# avga_TTH.net
KiCad netlist of a schematic drawn in EAGLE
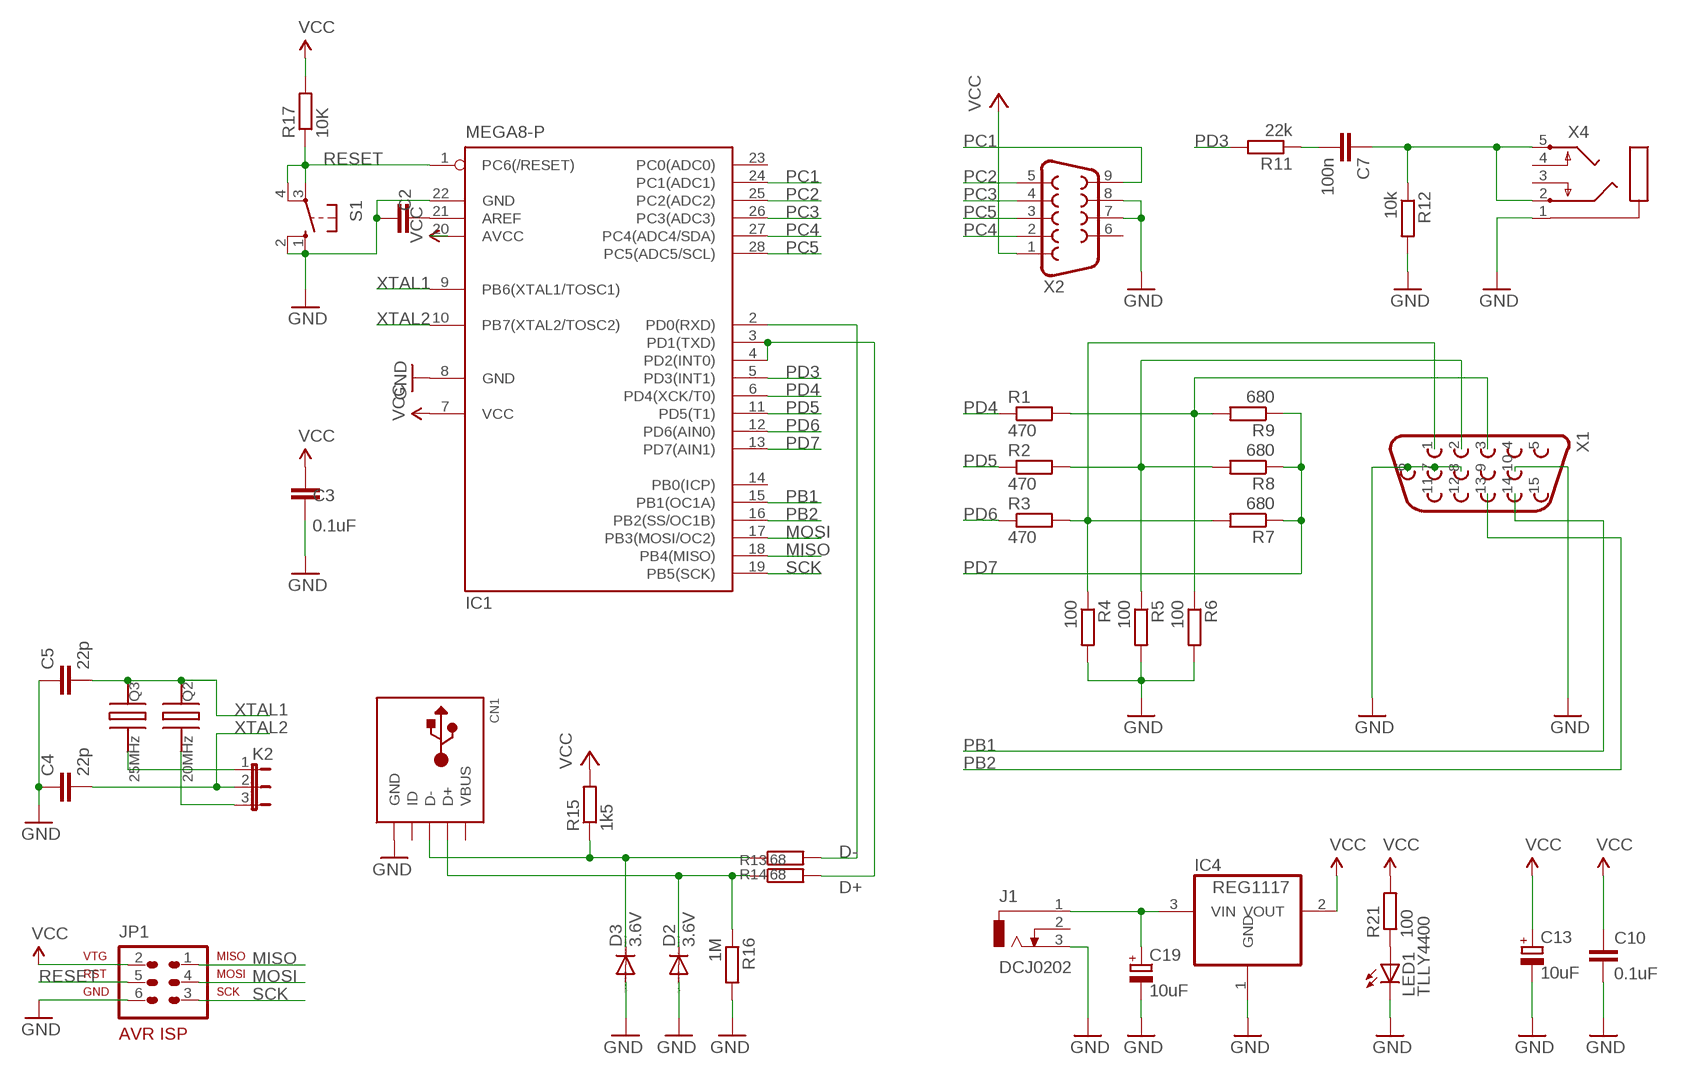
[diagram p0: schematic, sheet 1]

(export (version "E")
  (design (tool "Eeschema 10.0.6"))
  (components
    (comp (ref "C2")
      (value "0.1uF")
      (footprint "eagle-import:C0805")
      (libsource (lib "eagle-import") (part "resistor_C-EUC0805"))
    )
    (comp (ref "C3")
      (value "0.1uF")
      (footprint "eagle-import:C0805")
      (libsource (lib "eagle-import") (part "resistor_C-EUC0805"))
    )
    (comp (ref "C4")
      (value "22p")
      (footprint "eagle-import:C0805")
      (libsource (lib "eagle-import") (part "C-EUC0805"))
    )
    (comp (ref "C5")
      (value "22p")
      (footprint "eagle-import:C0805")
      (libsource (lib "eagle-import") (part "C-EUC0805"))
    )
    (comp (ref "C7")
      (value "100n")
      (footprint "eagle-import:C0805")
      (libsource (lib "eagle-import") (part "C-EUC0805"))
    )
    (comp (ref "C10")
      (value "0.1uF")
      (footprint "eagle-import:C0805")
      (libsource (lib "eagle-import") (part "C-EUC0805"))
    )
    (comp (ref "C13")
      (value "10uF")
      (footprint "eagle-import:E2,5-5")
      (libsource (lib "eagle-import") (part "CPOL-EUE2.5-5"))
    )
    (comp (ref "C19")
      (value "10uF")
      (footprint "eagle-import:E2,5-5")
      (libsource (lib "eagle-import") (part "CPOL-EUE2.5-5"))
    )
    (comp (ref "CN1")
      (value "USBMINIB")
      (footprint "eagle-import:USB-MINIB")
      (libsource (lib "eagle-import") (part "USBMINIB"))
    )
    (comp (ref "D2")
      (value "3.6V")
      (footprint "eagle-import:MINIMELF")
      (libsource (lib "eagle-import") (part "DIODE-MINIMELF"))
    )
    (comp (ref "D3")
      (value "3.6V")
      (footprint "eagle-import:MINIMELF")
      (libsource (lib "eagle-import") (part "DIODE-MINIMELF"))
    )
    (comp (ref "IC1")
      (value "MEGA8-P")
      (footprint "eagle-import:DIL28-3")
      (libsource (lib "eagle-import") (part "MEGA8-P"))
    )
    (comp (ref "IC4")
      (value "REG1117")
      (footprint "eagle-import:SOT223")
      (libsource (lib "eagle-import") (part "REG1117"))
    )
    (comp (ref "J1")
      (value "DCJ0202")
      (footprint "eagle-import:DCJ0202")
      (libsource (lib "eagle-import") (part "DCJ0202"))
    )
    (comp (ref "JP1")
      (value "AVR-ISP-6R")
      (footprint "eagle-import:AVR-ISP-6R")
      (libsource (lib "eagle-import") (part "AVR-ISP-6R"))
    )
    (comp (ref "K2")
      (value "CON-3-POL")
      (footprint "eagle-import:MOLEX-PSK-03")
      (libsource (lib "eagle-import") (part "CON-3-POL"))
    )
    (comp (ref "LED1")
      (value "TLLY4400")
      (footprint "eagle-import:LED3MM")
      (fields (field (name "MF") "VISHAY SEMICONDUCTOR"))
      (libsource (lib "eagle-import") (part "TLLY4400"))
    )
    (comp (ref "Q2")
      (value "20MHz")
      (footprint "eagle-import:QUARZ")
      (libsource (lib "eagle-import") (part "QUARZ"))
    )
    (comp (ref "Q3")
      (value "25MHz")
      (footprint "eagle-import:QUARZ")
      (libsource (lib "eagle-import") (part "QUARZ"))
    )
    (comp (ref "R1")
      (value "470")
      (footprint "eagle-import:R0805")
      (libsource (lib "eagle-import") (part "R-EU_R0805"))
    )
    (comp (ref "R2")
      (value "470")
      (footprint "eagle-import:R0805")
      (libsource (lib "eagle-import") (part "R-EU_R0805"))
    )
    (comp (ref "R3")
      (value "470")
      (footprint "eagle-import:R0805")
      (libsource (lib "eagle-import") (part "R-EU_R0805"))
    )
    (comp (ref "R4")
      (value "100")
      (footprint "eagle-import:R0805")
      (libsource (lib "eagle-import") (part "R-EU_R0805"))
    )
    (comp (ref "R5")
      (value "100")
      (footprint "eagle-import:R0805")
      (libsource (lib "eagle-import") (part "R-EU_R0805"))
    )
    (comp (ref "R6")
      (value "100")
      (footprint "eagle-import:R0805")
      (libsource (lib "eagle-import") (part "R-EU_R0805"))
    )
    (comp (ref "R7")
      (value "680")
      (footprint "eagle-import:R0805")
      (libsource (lib "eagle-import") (part "R-EU_R0805"))
    )
    (comp (ref "R8")
      (value "680")
      (footprint "eagle-import:R0805")
      (libsource (lib "eagle-import") (part "R-EU_R0805"))
    )
    (comp (ref "R9")
      (value "680")
      (footprint "eagle-import:R0805")
      (libsource (lib "eagle-import") (part "R-EU_R0805"))
    )
    (comp (ref "R11")
      (value "22k")
      (footprint "eagle-import:R0805")
      (libsource (lib "eagle-import") (part "R-EU_R0805"))
    )
    (comp (ref "R12")
      (value "10k")
      (footprint "eagle-import:R0805")
      (libsource (lib "eagle-import") (part "R-EU_R0805"))
    )
    (comp (ref "R13")
      (value "68")
      (footprint "eagle-import:R0805")
      (libsource (lib "eagle-import") (part "R-EU_R0805"))
    )
    (comp (ref "R14")
      (value "68")
      (footprint "eagle-import:R0805")
      (libsource (lib "eagle-import") (part "R-EU_R0805"))
    )
    (comp (ref "R15")
      (value "1k5")
      (footprint "eagle-import:R0805")
      (libsource (lib "eagle-import") (part "R-EU_R0805"))
    )
    (comp (ref "R16")
      (value "1M")
      (footprint "eagle-import:R0805")
      (libsource (lib "eagle-import") (part "R-EU_R0805"))
    )
    (comp (ref "R17")
      (value "10K")
      (footprint "eagle-import:R0805")
      (libsource (lib "eagle-import") (part "resistor_R-EU_R0805"))
    )
    (comp (ref "R21")
      (value "100")
      (footprint "eagle-import:R0805")
      (libsource (lib "eagle-import") (part "resistor_R-EU_R0805"))
    )
    (comp (ref "S1")
      (value "10-XX")
      (footprint "eagle-import:B3F-10XX")
      (fields (field (name "MPN") "B3F-1000"))
      (libsource (lib "eagle-import") (part "10-XX"))
    )
    (comp (ref "X1")
      (value "VGA-BU-15POL")
      (footprint "eagle-import:VGA-BU-15POL")
      (libsource (lib "eagle-import") (part "VGA-BU-15POL"))
    )
    (comp (ref "X2")
      (value "D-SUB-ST-9POL")
      (footprint "eagle-import:M09HP")
      (libsource (lib "eagle-import") (part "D-SUB-ST-9POL"))
    )
    (comp (ref "X4")
      (value "KLINKENBUCHSE")
      (footprint "eagle-import:KLINKENBUCHSE")
      (libsource (lib "eagle-import") (part "KLINKENBUCHSE"))
    )
  )
  (nets
    (net (code "1") (name "/MISO") (class "Default")
      (node (ref "IC1") (pin "18") (pinfunction "PB4(MISO)_18") (pintype "bidirectional"))
      (node (ref "JP1") (pin "1") (pinfunction "1_1") (pintype "passive"))
    )
    (net (code "2") (name "/MOSI") (class "Default")
      (node (ref "IC1") (pin "17") (pinfunction "PB3(MOSI/OC2)_17") (pintype "bidirectional"))
      (node (ref "JP1") (pin "4") (pinfunction "4_4") (pintype "passive"))
    )
    (net (code "3") (name "/PB1") (class "Default")
      (node (ref "IC1") (pin "15") (pinfunction "PB1(OC1A)_15") (pintype "bidirectional"))
      (node (ref "X1") (pin "14") (pinfunction "14_14") (pintype "passive"))
    )
    (net (code "4") (name "/PB2") (class "Default")
      (node (ref "IC1") (pin "16") (pinfunction "PB2(SS/OC1B)_16") (pintype "bidirectional"))
      (node (ref "X1") (pin "13") (pinfunction "13_13") (pintype "passive"))
    )
    (net (code "5") (name "/PC1") (class "Default")
      (node (ref "IC1") (pin "24") (pinfunction "PC1(ADC1)_24") (pintype "bidirectional"))
      (node (ref "X2") (pin "9") (pinfunction "9_9") (pintype "passive"))
    )
    (net (code "6") (name "/PC2") (class "Default")
      (node (ref "IC1") (pin "25") (pinfunction "PC2(ADC2)_25") (pintype "bidirectional"))
      (node (ref "X2") (pin "5") (pinfunction "5_5") (pintype "passive"))
    )
    (net (code "7") (name "/PC3") (class "Default")
      (node (ref "IC1") (pin "26") (pinfunction "PC3(ADC3)_26") (pintype "bidirectional"))
      (node (ref "X2") (pin "4") (pinfunction "4_4") (pintype "passive"))
    )
    (net (code "8") (name "/PC4") (class "Default")
      (node (ref "IC1") (pin "27") (pinfunction "PC4(ADC4/SDA)_27") (pintype "bidirectional"))
      (node (ref "X2") (pin "2") (pinfunction "2_2") (pintype "passive"))
    )
    (net (code "9") (name "/PC5") (class "Default")
      (node (ref "IC1") (pin "28") (pinfunction "PC5(ADC5/SCL)_28") (pintype "bidirectional"))
      (node (ref "X2") (pin "3") (pinfunction "3_3") (pintype "passive"))
    )
    (net (code "10") (name "/PD3") (class "Default")
      (node (ref "IC1") (pin "5") (pinfunction "PD3(INT1)_5") (pintype "bidirectional"))
      (node (ref "R11") (pin "2") (pinfunction "2_2") (pintype "passive"))
    )
    (net (code "11") (name "/PD4") (class "Default")
      (node (ref "IC1") (pin "6") (pinfunction "PD4(XCK/T0)_6") (pintype "bidirectional"))
      (node (ref "R1") (pin "1") (pinfunction "1_1") (pintype "passive"))
    )
    (net (code "12") (name "/PD5") (class "Default")
      (node (ref "IC1") (pin "11") (pinfunction "PD5(T1)_11") (pintype "bidirectional"))
      (node (ref "R2") (pin "1") (pinfunction "1_1") (pintype "passive"))
    )
    (net (code "13") (name "/PD6") (class "Default")
      (node (ref "IC1") (pin "12") (pinfunction "PD6(AIN0)_12") (pintype "bidirectional"))
      (node (ref "R3") (pin "1") (pinfunction "1_1") (pintype "passive"))
    )
    (net (code "14") (name "/PD7") (class "Default")
      (node (ref "IC1") (pin "13") (pinfunction "PD7(AIN1)_13") (pintype "bidirectional"))
      (node (ref "R7") (pin "1") (pinfunction "1_1") (pintype "passive"))
      (node (ref "R8") (pin "1") (pinfunction "1_1") (pintype "passive"))
      (node (ref "R9") (pin "1") (pinfunction "1_1") (pintype "passive"))
    )
    (net (code "15") (name "/RESET") (class "Default")
      (node (ref "IC1") (pin "1") (pinfunction "PC6(/RESET)_1") (pintype "bidirectional"))
      (node (ref "JP1") (pin "5") (pinfunction "5_5") (pintype "passive"))
      (node (ref "R17") (pin "1") (pinfunction "1_1") (pintype "passive"))
      (node (ref "S1") (pin "3") (pinfunction "P_3") (pintype "passive"))
      (node (ref "S1") (pin "4") (pinfunction "P1_4") (pintype "passive"))
    )
    (net (code "16") (name "/SCK") (class "Default")
      (node (ref "IC1") (pin "19") (pinfunction "PB5(SCK)_19") (pintype "bidirectional"))
      (node (ref "JP1") (pin "3") (pinfunction "3_3") (pintype "passive"))
    )
    (net (code "17") (name "/VBUS") (class "Default")
      (node (ref "CN1") (pin "VBUS") (pinfunction "VBUS_VBUS") (pintype "power_in"))
    )
    (net (code "18") (name "/XTAL1") (class "Default")
      (node (ref "C5") (pin "2") (pinfunction "2_2") (pintype "passive"))
      (node (ref "IC1") (pin "9") (pinfunction "PB6(XTAL1/TOSC1)_9") (pintype "bidirectional"))
      (node (ref "Q2") (pin "1") (pinfunction "1_1") (pintype "passive"))
      (node (ref "Q3") (pin "1") (pinfunction "1_1") (pintype "passive"))
    )
    (net (code "19") (name "/XTAL2") (class "Default")
      (node (ref "C4") (pin "2") (pinfunction "2_2") (pintype "passive"))
      (node (ref "IC1") (pin "10") (pinfunction "PB7(XTAL2/TOSC2)_10") (pintype "bidirectional"))
      (node (ref "K2") (pin "2") (pinfunction "2_2") (pintype "passive"))
    )
    (net (code "20") (name "GND") (class "Default")
      (node (ref "C10") (pin "2") (pinfunction "2_2") (pintype "passive"))
      (node (ref "C13") (pin "-") (pinfunction "-_-") (pintype "passive"))
      (node (ref "C19") (pin "-") (pinfunction "-_-") (pintype "passive"))
      (node (ref "C2") (pin "2") (pinfunction "2_2") (pintype "passive"))
      (node (ref "C3") (pin "1") (pinfunction "1_1") (pintype "passive"))
      (node (ref "C4") (pin "1") (pinfunction "1_1") (pintype "passive"))
      (node (ref "C5") (pin "1") (pinfunction "1_1") (pintype "passive"))
      (node (ref "CN1") (pin "GND") (pinfunction "GND_GND") (pintype "power_in"))
      (node (ref "D2") (pin "A") (pinfunction "A_A") (pintype "passive"))
      (node (ref "D3") (pin "A") (pinfunction "A_A") (pintype "passive"))
      (node (ref "IC1") (pin "22") (pinfunction "GND_22") (pintype "power_in"))
      (node (ref "IC1") (pin "8") (pinfunction "GND_8") (pintype "power_in"))
      (node (ref "IC4") (pin "1") (pinfunction "GND_1") (pintype "power_in"))
      (node (ref "J1") (pin "3") (pinfunction "3_3") (pintype "passive"))
      (node (ref "JP1") (pin "6") (pinfunction "6_6") (pintype "passive"))
      (node (ref "LED1") (pin "K") (pinfunction "C_K") (pintype "passive"))
      (node (ref "R12") (pin "2") (pinfunction "2_2") (pintype "passive"))
      (node (ref "R16") (pin "2") (pinfunction "2_2") (pintype "passive"))
      (node (ref "R4") (pin "2") (pinfunction "2_2") (pintype "passive"))
      (node (ref "R5") (pin "2") (pinfunction "2_2") (pintype "passive"))
      (node (ref "R6") (pin "2") (pinfunction "2_2") (pintype "passive"))
      (node (ref "S1") (pin "1") (pinfunction "S_1") (pintype "passive"))
      (node (ref "S1") (pin "2") (pinfunction "S1_2") (pintype "passive"))
      (node (ref "X1") (pin "10") (pinfunction "10_10") (pintype "passive"))
      (node (ref "X1") (pin "6") (pinfunction "6_6") (pintype "passive"))
      (node (ref "X1") (pin "7") (pinfunction "7_7") (pintype "passive"))
      (node (ref "X1") (pin "8") (pinfunction "8_8") (pintype "passive"))
      (node (ref "X2") (pin "7") (pinfunction "7_7") (pintype "passive"))
      (node (ref "X2") (pin "8") (pinfunction "8_8") (pintype "passive"))
      (node (ref "X4") (pin "1") (pinfunction "1_1") (pintype "passive"))
    )
    (net (code "21") (name "Net-(C7-Pad1)") (class "Default")
      (node (ref "C7") (pin "1") (pinfunction "1_1") (pintype "passive"))
      (node (ref "R12") (pin "1") (pinfunction "1_1") (pintype "passive"))
      (node (ref "X4") (pin "2") (pinfunction "2_2") (pintype "passive"))
      (node (ref "X4") (pin "5") (pinfunction "5_5") (pintype "passive"))
    )
    (net (code "22") (name "Net-(C7-Pad2)") (class "Default")
      (node (ref "C7") (pin "2") (pinfunction "2_2") (pintype "passive"))
      (node (ref "R11") (pin "1") (pinfunction "1_1") (pintype "passive"))
    )
    (net (code "23") (name "Net-(CN1-PadD+)") (class "Default")
      (node (ref "CN1") (pin "D+") (pinfunction "D+_D+") (pintype "bidirectional"))
      (node (ref "D2") (pin "C") (pinfunction "C_C") (pintype "passive"))
      (node (ref "R13") (pin "1") (pinfunction "1_1") (pintype "passive"))
      (node (ref "R16") (pin "1") (pinfunction "1_1") (pintype "passive"))
    )
    (net (code "24") (name "Net-(CN1-PadD-)") (class "Default")
      (node (ref "CN1") (pin "D-") (pinfunction "D-_D-") (pintype "bidirectional"))
      (node (ref "D3") (pin "C") (pinfunction "C_C") (pintype "passive"))
      (node (ref "R14") (pin "1") (pinfunction "1_1") (pintype "passive"))
      (node (ref "R15") (pin "1") (pinfunction "1_1") (pintype "passive"))
    )
    (net (code "25") (name "Net-(IC1-AREF)") (class "Default")
      (node (ref "C2") (pin "1") (pinfunction "1_1") (pintype "passive"))
      (node (ref "IC1") (pin "21") (pinfunction "AREF_21") (pintype "passive"))
    )
    (net (code "26") (name "Net-(IC1-PD0(RXD))") (class "Default")
      (node (ref "IC1") (pin "2") (pinfunction "PD0(RXD)_2") (pintype "bidirectional"))
      (node (ref "R14") (pin "2") (pinfunction "2_2") (pintype "passive"))
    )
    (net (code "27") (name "Net-(IC1-PD1(TXD))") (class "Default")
      (node (ref "IC1") (pin "3") (pinfunction "PD1(TXD)_3") (pintype "bidirectional"))
      (node (ref "IC1") (pin "4") (pinfunction "PD2(INT0)_4") (pintype "bidirectional"))
      (node (ref "R13") (pin "2") (pinfunction "2_2") (pintype "passive"))
    )
    (net (code "28") (name "Net-(IC4-VIN)") (class "Default")
      (node (ref "C19") (pin "+") (pinfunction "+_+") (pintype "passive"))
      (node (ref "IC4") (pin "3") (pinfunction "VIN_3") (pintype "input"))
      (node (ref "J1") (pin "1") (pinfunction "1_1") (pintype "passive"))
    )
    (net (code "29") (name "Net-(K2-Pad1)") (class "Default")
      (node (ref "K2") (pin "1") (pinfunction "1_1") (pintype "passive"))
      (node (ref "Q3") (pin "2") (pinfunction "2_2") (pintype "passive"))
    )
    (net (code "30") (name "Net-(K2-Pad3)") (class "Default")
      (node (ref "K2") (pin "3") (pinfunction "3_3") (pintype "passive"))
      (node (ref "Q2") (pin "2") (pinfunction "2_2") (pintype "passive"))
    )
    (net (code "31") (name "Net-(LED1-PadA)") (class "Default")
      (node (ref "LED1") (pin "A") (pinfunction "A_A") (pintype "passive"))
      (node (ref "R21") (pin "1") (pinfunction "1_1") (pintype "passive"))
    )
    (net (code "32") (name "Net-(R1-Pad2)") (class "Default")
      (node (ref "R1") (pin "2") (pinfunction "2_2") (pintype "passive"))
      (node (ref "R6") (pin "1") (pinfunction "1_1") (pintype "passive"))
      (node (ref "R9") (pin "2") (pinfunction "2_2") (pintype "passive"))
      (node (ref "X1") (pin "3") (pinfunction "3_3") (pintype "passive"))
    )
    (net (code "33") (name "Net-(R2-Pad2)") (class "Default")
      (node (ref "R2") (pin "2") (pinfunction "2_2") (pintype "passive"))
      (node (ref "R5") (pin "1") (pinfunction "1_1") (pintype "passive"))
      (node (ref "R8") (pin "2") (pinfunction "2_2") (pintype "passive"))
      (node (ref "X1") (pin "2") (pinfunction "2_2") (pintype "passive"))
    )
    (net (code "34") (name "Net-(R3-Pad2)") (class "Default")
      (node (ref "R3") (pin "2") (pinfunction "2_2") (pintype "passive"))
      (node (ref "R4") (pin "1") (pinfunction "1_1") (pintype "passive"))
      (node (ref "R7") (pin "2") (pinfunction "2_2") (pintype "passive"))
      (node (ref "X1") (pin "1") (pinfunction "1_1") (pintype "passive"))
    )
    (net (code "35") (name "VCC") (class "Default")
      (node (ref "C10") (pin "1") (pinfunction "1_1") (pintype "passive"))
      (node (ref "C13") (pin "+") (pinfunction "+_+") (pintype "passive"))
      (node (ref "C3") (pin "2") (pinfunction "2_2") (pintype "passive"))
      (node (ref "IC1") (pin "20") (pinfunction "AVCC_20") (pintype "power_in"))
      (node (ref "IC1") (pin "7") (pinfunction "VCC_7") (pintype "power_in"))
      (node (ref "IC4") (pin "2") (pinfunction "VOUT_2") (pintype "output"))
      (node (ref "JP1") (pin "2") (pinfunction "2_2") (pintype "passive"))
      (node (ref "R15") (pin "2") (pinfunction "2_2") (pintype "passive"))
      (node (ref "R17") (pin "2") (pinfunction "2_2") (pintype "passive"))
      (node (ref "R21") (pin "2") (pinfunction "2_2") (pintype "passive"))
      (node (ref "X2") (pin "1") (pinfunction "1_1") (pintype "passive"))
    )
    (net (code "36") (name "unconnected-(CN1-PadID)") (class "Default")
      (node (ref "CN1") (pin "ID") (pinfunction "ID_ID") (pintype "bidirectional"))
    )
    (net (code "37") (name "unconnected-(IC1-PB0(ICP)-Pad14)") (class "Default")
      (node (ref "IC1") (pin "14") (pinfunction "PB0(ICP)_14") (pintype "bidirectional"))
    )
    (net (code "38") (name "unconnected-(IC1-PC0(ADC0)-Pad23)") (class "Default")
      (node (ref "IC1") (pin "23") (pinfunction "PC0(ADC0)_23") (pintype "bidirectional"))
    )
    (net (code "39") (name "unconnected-(J1-Pad2)") (class "Default")
      (node (ref "J1") (pin "2") (pinfunction "2_2") (pintype "passive"))
    )
    (net (code "40") (name "unconnected-(X1-Pad4)") (class "Default")
      (node (ref "X1") (pin "4") (pinfunction "4_4") (pintype "passive"))
    )
    (net (code "41") (name "unconnected-(X1-Pad5)") (class "Default")
      (node (ref "X1") (pin "5") (pinfunction "5_5") (pintype "passive"))
    )
    (net (code "42") (name "unconnected-(X1-Pad9)") (class "Default")
      (node (ref "X1") (pin "9") (pinfunction "9_9") (pintype "passive"))
    )
    (net (code "43") (name "unconnected-(X1-Pad11)") (class "Default")
      (node (ref "X1") (pin "11") (pinfunction "11_11") (pintype "passive"))
    )
    (net (code "44") (name "unconnected-(X1-Pad12)") (class "Default")
      (node (ref "X1") (pin "12") (pinfunction "12_12") (pintype "passive"))
    )
    (net (code "45") (name "unconnected-(X1-Pad15)") (class "Default")
      (node (ref "X1") (pin "15") (pinfunction "15_15") (pintype "passive"))
    )
    (net (code "46") (name "unconnected-(X2-Pad6)") (class "Default")
      (node (ref "X2") (pin "6") (pinfunction "6_6") (pintype "passive"))
    )
    (net (code "47") (name "unconnected-(X4-Pad3)") (class "Default")
      (node (ref "X4") (pin "3") (pinfunction "3_3") (pintype "passive"))
    )
    (net (code "48") (name "unconnected-(X4-Pad4)") (class "Default")
      (node (ref "X4") (pin "4") (pinfunction "4_4") (pintype "passive"))
    )
  )
)
